# STM32G030_HeaderBoardSCH.net
KiCad netlist of a schematic drawn in Altium Designer
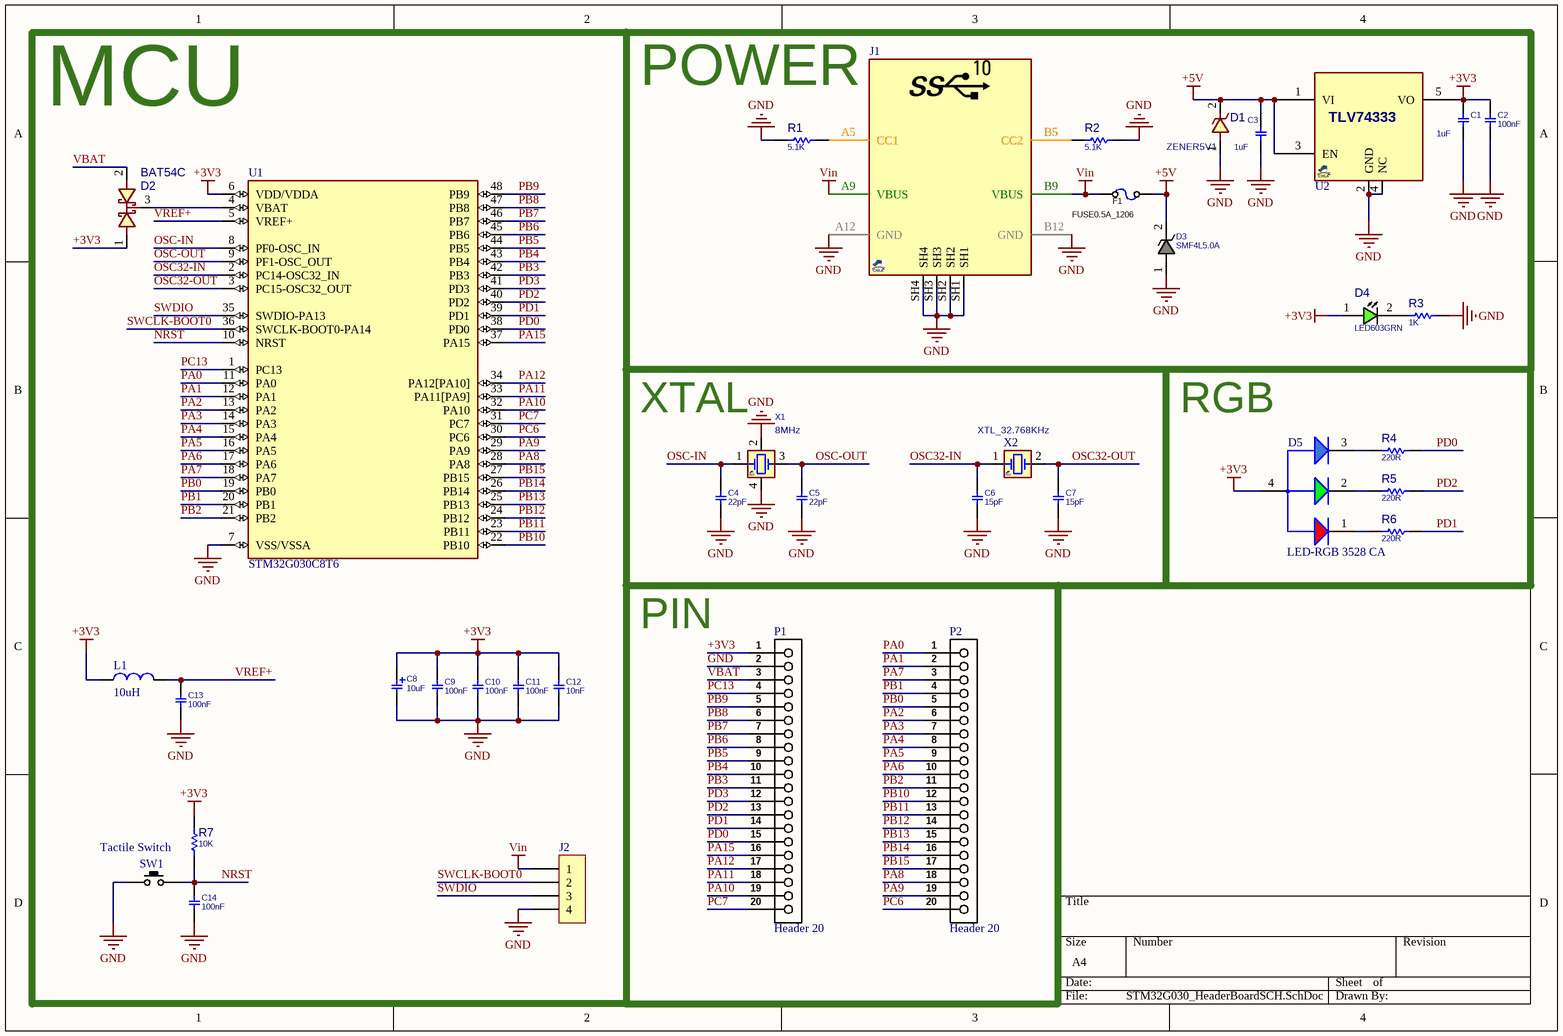
[diagram p0: STM32G030_HeaderBoardSCH.SchDoc]

(export (version "E")
  (design (tool "Eeschema 10.0.6"))
  (components
    (comp (ref "C1")
      (value "1uF")
      (footprint "C0603")
      (description "CAP, MLCC, -F, -V, MATERIAL, -%, 0201")
      (fields (field (name "MANF_P#") "MANF_PART#"))
      (libsource (lib "passive_smd") (part "CAP_SMD_MLCC_0603"))
    )
    (comp (ref "C2")
      (value "100nF")
      (footprint "C0603")
      (description "CAP, MLCC, -F, -V, MATERIAL, -%, 0201")
      (fields (field (name "MANF_P#") "MANF_PART#"))
      (libsource (lib "passive_smd") (part "CAP_SMD_MLCC_0603"))
    )
    (comp (ref "C3")
      (value "1uF")
      (footprint "C0603")
      (description "CAP, MLCC, -F, -V, MATERIAL, -%, 0201")
      (fields (field (name "MANF_P#") "MANF_PART#"))
      (libsource (lib "passive_smd") (part "CAP_SMD_MLCC_0603"))
    )
    (comp (ref "C4")
      (value "22pF")
      (footprint "C0603")
      (description "CAP, MLCC, -F, -V, MATERIAL, -%, 0201")
      (fields (field (name "MANF_P#") "MANF_PART#"))
      (libsource (lib "passive_smd") (part "CAP_SMD_MLCC_0603"))
    )
    (comp (ref "C5")
      (value "22pF")
      (footprint "C0603")
      (description "CAP, MLCC, -F, -V, MATERIAL, -%, 0201")
      (fields (field (name "MANF_P#") "MANF_PART#"))
      (libsource (lib "passive_smd") (part "CAP_SMD_MLCC_0603"))
    )
    (comp (ref "C6")
      (value "15pF")
      (footprint "C0603")
      (description "CAP, MLCC, -F, -V, MATERIAL, -%, 0201")
      (fields (field (name "MANF_P#") "MANF_PART#"))
      (libsource (lib "passive_smd") (part "CAP_SMD_MLCC_0603"))
    )
    (comp (ref "C7")
      (value "15pF")
      (footprint "C0603")
      (description "CAP, MLCC, -F, -V, MATERIAL, -%, 0201")
      (fields (field (name "MANF_P#") "MANF_PART#"))
      (libsource (lib "passive_smd") (part "CAP_SMD_MLCC_0603"))
    )
    (comp (ref "C8")
      (value "10uF")
      (footprint "C_TN_3216")
      (description "CAP, SMD, TAN,")
      (libsource (lib "passive_smd") (part "CAP_SMD_TAN"))
    )
    (comp (ref "C9")
      (value "100nF")
      (footprint "C0603")
      (description "CAP, MLCC, -F, -V, MATERIAL, -%, 0201")
      (fields (field (name "MANF_P#") "MANF_PART#"))
      (libsource (lib "passive_smd") (part "CAP_SMD_MLCC_0603"))
    )
    (comp (ref "C10")
      (value "100nF")
      (footprint "C0603")
      (description "CAP, MLCC, -F, -V, MATERIAL, -%, 0201")
      (fields (field (name "MANF_P#") "MANF_PART#"))
      (libsource (lib "passive_smd") (part "CAP_SMD_MLCC_0603"))
    )
    (comp (ref "C11")
      (value "100nF")
      (footprint "C0603")
      (description "CAP, MLCC, -F, -V, MATERIAL, -%, 0201")
      (fields (field (name "MANF_P#") "MANF_PART#"))
      (libsource (lib "passive_smd") (part "CAP_SMD_MLCC_0603"))
    )
    (comp (ref "C12")
      (value "10nF")
      (footprint "C0603")
      (description "CAP, MLCC, -F, -V, MATERIAL, -%, 0201")
      (fields (field (name "MANF_P#") "MANF_PART#"))
      (libsource (lib "passive_smd") (part "CAP_SMD_MLCC_0603"))
    )
    (comp (ref "C13")
      (value "100nF")
      (footprint "C0603")
      (description "CAP, MLCC, -F, -V, MATERIAL, -%, 0201")
      (fields (field (name "MANF_P#") "MANF_PART#"))
      (libsource (lib "passive_smd") (part "CAP_SMD_MLCC_0603"))
    )
    (comp (ref "C14")
      (value "100nF")
      (footprint "C0603")
      (description "CAP, MLCC, -F, -V, MATERIAL, -%, 0201")
      (fields (field (name "MANF_P#") "MANF_PART#"))
      (libsource (lib "passive_smd") (part "CAP_SMD_MLCC_0603"))
    )
    (comp (ref "D1")
      (value "ZENER5V1")
      (footprint "D_SOD123W")
      (description "DIODE, ZENER, 1W, 5.1V")
      (fields (field (name "MANF") "Diodes") (field (name "MANF_P#") "BZT52HC5V1WF-7"))
      (libsource (lib "AVR_RCS") (part "DIODE_SMD_ZENER_BZT52HC5V1"))
    )
    (comp (ref "D2")
      (value "BAT54C")
      (footprint "SOT23_3")
      (description "DIODE, SCHOTTKY, DUAL, 30V, 0.2A")
      (fields (field (name "MANF") "Diodes") (field (name "MANF_P#") "BAT54C-7-F"))
      (libsource (lib "diode") (part "DIODE_SMD_SCHOTTKY_BAT54C"))
    )
    (comp (ref "D3")
      (value "SMF4L5.0A")
      (footprint "D_SOD123W")
      (description "TVS, ESD PROTECT")
      (fields (field (name "MANF_P#") "TPSMF4L33A") (field (name "MANF") "Littelfuse"))
      (libsource (lib "protect_tvs_esd_fuse") (part "TVS_TPSMF4L33A"))
    )
    (comp (ref "D4")
      (value "LED603GRN")
      (footprint "LED0603GRN")
      (description "LED, SMD, 0603, GREEN")
      (fields (field (name "MANF") "Kingbright") (field (name "MANF_P#") "APT1608SGC"))
      (libsource (lib "led(diode)") (part "LED_SMD_0603_GRN"))
    )
    (comp (ref "D5")
      (value "LED-RGB 3528 CA")
      (footprint "LED-RGB 3528 CA")
      (description "LED SMD 3528 RGB-CA")
      (libsource (lib "Mehrdad") (part "LED-RGB 3528 CA"))
    )
    (comp (ref "F1")
      (value "FUSE0.5A_1206")
      (footprint "F1206")
      (description "Fuse, 3A, 32VDC, 1206, SMD, Slow Blow")
      (fields (field (name "MANF") "Bourns") (field (name "MANF_P#") "SF-1206SP300-2"))
      (libsource (lib "protect_tvs_esd_fuse") (part "FUSE_3A_1206_SLOW"))
    )
    (comp (ref "J1")
      (value "UJC-HP-3-SMT")
      (footprint "USBC_SMD_6_UJCHP3SMT")
      (description "CONN, USB, Type C (USB 3.1), Right-Angle, SMD")
      (fields (field (name "MANF") "CUI Devices"))
      (libsource (lib "conn_usbc") (part "CONN_USBC_SMD_6_UJC-HP-3-SMT"))
    )
    (comp (ref "J2")
      (value "4b")
      (footprint "HDR_THT_4M_2.54mm_RA")
      (description "Header, single row, 4 pin")
      (fields (field (name "VALIDATION") "NT"))
      (libsource (lib "aKaReZa") (part "Con_MPH_4x1_V_THT_2.54"))
    )
    (comp (ref "L1")
      (value "10uH")
      (footprint "0603_L")
      (description "Inductor")
      (fields (field (name "VALIDATION") "Valid"))
      (libsource (lib "aKaReZa") (part "Ind_SMD"))
    )
    (comp (ref "P1")
      (value "Header 20")
      (footprint "HDR 1X20 Male Top")
      (fields (field (name "PUBLISHER") "Majid Derhambakhsh"))
      (libsource (lib "mBedLab Altium Library (2024-04-20)") (part "Header 20"))
    )
    (comp (ref "P2")
      (value "Header 20")
      (footprint "HDR 1X20 Male Top")
      (fields (field (name "PUBLISHER") "Majid Derhambakhsh"))
      (libsource (lib "mBedLab Altium Library (2024-04-20)") (part "Header 20"))
    )
    (comp (ref "R1")
      (value "5.1K")
      (footprint "R0603")
      (description "RESISTOR, SMD")
      (libsource (lib "passive_smd") (part "RES_SMD_0603"))
    )
    (comp (ref "R2")
      (value "5.1K")
      (footprint "R0603")
      (description "RESISTOR, SMD")
      (libsource (lib "passive_smd") (part "RES_SMD_0603"))
    )
    (comp (ref "R3")
      (value "1K")
      (footprint "R0603")
      (description "RESISTOR, SMD")
      (libsource (lib "passive_smd") (part "RES_SMD_0603"))
    )
    (comp (ref "R4")
      (value "220R")
      (footprint "R0603")
      (description "RESISTOR, SMD")
      (libsource (lib "passive_smd") (part "RES_SMD_0603"))
    )
    (comp (ref "R5")
      (value "220R")
      (footprint "R0603")
      (description "RESISTOR, SMD")
      (libsource (lib "passive_smd") (part "RES_SMD_0603"))
    )
    (comp (ref "R6")
      (value "220R")
      (footprint "R0603")
      (description "RESISTOR, SMD")
      (libsource (lib "passive_smd") (part "RES_SMD_0603"))
    )
    (comp (ref "R7")
      (value "10K")
      (footprint "R0603")
      (description "RESISTOR, SMD")
      (libsource (lib "passive_smd") (part "RES_SMD_0603"))
    )
    (comp (ref "SW1")
      (value "Tactile Switch")
      (footprint "Tactil Switch 3*4*2")
      (description "3x6x5 mm - 2 Pin")
      (libsource (lib "Mehrdad") (part "Tactile Switch"))
    )
    (comp (ref "U1")
      (value "STM32G030C8T6")
      (footprint "STM32G030C8T6")
      (libsource (lib "Mehrdad") (part "STM32G030C8T6"))
    )
    (comp (ref "U2")
      (value "TLV74333")
      (footprint "SOT23_5")
      (description "REG, Linear, LDO0.12V, Fixed, 300mA, VIN1.4~5.5V, VOUT1~5.5V, SOT-23-5")
      (fields (field (name "MANF") "Texas Instruments") (field (name "MANF_P#") "TLV74333PDQN"))
      (libsource (lib "pwr_reg_linear_LDO_highPSRR") (part "VREG_TLV74333_SOT23"))
    )
    (comp (ref "X1")
      (value "8MHz")
      (footprint "XTL_4_3225")
      (description "Crystal 8MHz")
      (fields (field (name "MANF") "ECS") (field (name "MANF_P#") "ECS-80-18-33-JGN-TR"))
      (libsource (lib "crystal") (part "XTL_4_8MHz_3225"))
    )
    (comp (ref "X2")
      (value "XTL_32.768KHz")
      (footprint "XTL_2_3215")
      (description "Crystal, 32.768KHz, 3pF, 20PPM")
      (fields (field (name "MANF") "ABRACON") (field (name "MANF_P#") "ABS07W-32.768kHz-D-2-T"))
      (libsource (lib "crystal") (part "XTL_2_32.768_3215A"))
    )
  )
  (nets
    (net (code "1") (name "+3V3") (class "Default")
      (node (ref "C1") (pin "2") (pinfunction "2_2") (pintype "passive"))
      (node (ref "C10") (pin "2") (pinfunction "2_2") (pintype "passive"))
      (node (ref "C11") (pin "2") (pinfunction "2_2") (pintype "passive"))
      (node (ref "C12") (pin "2") (pinfunction "2_2") (pintype "passive"))
      (node (ref "C2") (pin "2") (pinfunction "2_2") (pintype "passive"))
      (node (ref "C8") (pin "1") (pinfunction "1_1") (pintype "passive"))
      (node (ref "C9") (pin "2") (pinfunction "2_2") (pintype "passive"))
      (node (ref "D2") (pin "1") (pinfunction "1_1") (pintype "passive"))
      (node (ref "D4") (pin "1") (pinfunction "ANODE_1") (pintype "passive"))
      (node (ref "D5") (pin "4") (pinfunction "COMM_ANODE_4") (pintype "passive"))
      (node (ref "L1") (pin "1") (pinfunction "1_1") (pintype "passive"))
      (node (ref "P1") (pin "1") (pinfunction "1_1") (pintype "passive"))
      (node (ref "R7") (pin "2") (pinfunction "2_2") (pintype "passive"))
      (node (ref "U1") (pin "6") (pinfunction "VDD/VDDA_6") (pintype "bidirectional"))
      (node (ref "U2") (pin "5") (pinfunction "VO_5") (pintype "passive"))
    )
    (net (code "2") (name "+5V") (class "Default")
      (node (ref "C3") (pin "2") (pinfunction "2_2") (pintype "passive"))
      (node (ref "D1") (pin "2") (pinfunction "2_2") (pintype "passive"))
      (node (ref "D3") (pin "2") (pinfunction "2_2") (pintype "passive"))
      (node (ref "F1") (pin "2") (pinfunction "2_2") (pintype "passive"))
      (node (ref "U2") (pin "1") (pinfunction "VI_1") (pintype "passive"))
      (node (ref "U2") (pin "3") (pinfunction "EN_3") (pintype "passive"))
    )
    (net (code "3") (name "/NRST") (class "Default")
      (node (ref "C14") (pin "2") (pinfunction "2_2") (pintype "passive"))
      (node (ref "R7") (pin "1") (pinfunction "1_1") (pintype "passive"))
      (node (ref "SW1") (pin "2") (pinfunction "P3_2") (pintype "passive"))
      (node (ref "U1") (pin "10") (pinfunction "NRST_10") (pintype "bidirectional"))
    )
    (net (code "4") (name "/OSC-IN") (class "Default")
      (node (ref "C4") (pin "2") (pinfunction "2_2") (pintype "passive"))
      (node (ref "U1") (pin "8") (pinfunction "PF0-OSC_IN_8") (pintype "bidirectional"))
      (node (ref "X1") (pin "1") (pinfunction "1_1") (pintype "passive"))
    )
    (net (code "5") (name "/OSC-OUT") (class "Default")
      (node (ref "C5") (pin "2") (pinfunction "2_2") (pintype "passive"))
      (node (ref "U1") (pin "9") (pinfunction "PF1-OSC_OUT_9") (pintype "bidirectional"))
      (node (ref "X1") (pin "3") (pinfunction "2_3") (pintype "passive"))
    )
    (net (code "6") (name "/OSC32-IN") (class "Default")
      (node (ref "C6") (pin "2") (pinfunction "2_2") (pintype "passive"))
      (node (ref "U1") (pin "2") (pinfunction "PC14-OSC32_IN_2") (pintype "bidirectional"))
      (node (ref "X2") (pin "1") (pinfunction "OSC1_1") (pintype "passive"))
    )
    (net (code "7") (name "/OSC32-OUT") (class "Default")
      (node (ref "C7") (pin "2") (pinfunction "2_2") (pintype "passive"))
      (node (ref "U1") (pin "3") (pinfunction "PC15-OSC32_OUT_3") (pintype "bidirectional"))
      (node (ref "X2") (pin "2") (pinfunction "OSC2_2") (pintype "passive"))
    )
    (net (code "8") (name "/PA0") (class "Default")
      (node (ref "P2") (pin "1") (pinfunction "1_1") (pintype "passive"))
      (node (ref "U1") (pin "11") (pinfunction "PA0_11") (pintype "bidirectional"))
    )
    (net (code "9") (name "/PA1") (class "Default")
      (node (ref "P2") (pin "2") (pinfunction "2_2") (pintype "passive"))
      (node (ref "U1") (pin "12") (pinfunction "PA1_12") (pintype "bidirectional"))
    )
    (net (code "10") (name "/PA2") (class "Default")
      (node (ref "P2") (pin "6") (pinfunction "6_6") (pintype "passive"))
      (node (ref "U1") (pin "13") (pinfunction "PA2_13") (pintype "bidirectional"))
    )
    (net (code "11") (name "/PA3") (class "Default")
      (node (ref "P2") (pin "7") (pinfunction "7_7") (pintype "passive"))
      (node (ref "U1") (pin "14") (pinfunction "PA3_14") (pintype "bidirectional"))
    )
    (net (code "12") (name "/PA4") (class "Default")
      (node (ref "P2") (pin "8") (pinfunction "8_8") (pintype "passive"))
      (node (ref "U1") (pin "15") (pinfunction "PA4_15") (pintype "bidirectional"))
    )
    (net (code "13") (name "/PA5") (class "Default")
      (node (ref "P2") (pin "9") (pinfunction "9_9") (pintype "passive"))
      (node (ref "U1") (pin "16") (pinfunction "PA5_16") (pintype "bidirectional"))
    )
    (net (code "14") (name "/PA6") (class "Default")
      (node (ref "P2") (pin "10") (pinfunction "10_10") (pintype "passive"))
      (node (ref "U1") (pin "17") (pinfunction "PA6_17") (pintype "bidirectional"))
    )
    (net (code "15") (name "/PA7") (class "Default")
      (node (ref "P2") (pin "3") (pinfunction "3_3") (pintype "passive"))
      (node (ref "U1") (pin "18") (pinfunction "PA7_18") (pintype "bidirectional"))
    )
    (net (code "16") (name "/PA8") (class "Default")
      (node (ref "P2") (pin "18") (pinfunction "18_18") (pintype "passive"))
      (node (ref "U1") (pin "28") (pinfunction "PA8_28") (pintype "bidirectional"))
    )
    (net (code "17") (name "/PA9") (class "Default")
      (node (ref "P2") (pin "19") (pinfunction "19_19") (pintype "passive"))
      (node (ref "U1") (pin "29") (pinfunction "PA9_29") (pintype "bidirectional"))
    )
    (net (code "18") (name "/PA10") (class "Default")
      (node (ref "P1") (pin "19") (pinfunction "19_19") (pintype "passive"))
      (node (ref "U1") (pin "32") (pinfunction "PA10_32") (pintype "bidirectional"))
    )
    (net (code "19") (name "/PA11") (class "Default")
      (node (ref "P1") (pin "18") (pinfunction "18_18") (pintype "passive"))
      (node (ref "U1") (pin "33") (pinfunction "PA11[PA9]_33") (pintype "bidirectional"))
    )
    (net (code "20") (name "/PA12") (class "Default")
      (node (ref "P1") (pin "17") (pinfunction "17_17") (pintype "passive"))
      (node (ref "U1") (pin "34") (pinfunction "PA12[PA10]_34") (pintype "bidirectional"))
    )
    (net (code "21") (name "/PA15") (class "Default")
      (node (ref "P1") (pin "16") (pinfunction "16_16") (pintype "passive"))
      (node (ref "U1") (pin "37") (pinfunction "PA15_37") (pintype "bidirectional"))
    )
    (net (code "22") (name "/PB0") (class "Default")
      (node (ref "P2") (pin "5") (pinfunction "5_5") (pintype "passive"))
      (node (ref "U1") (pin "19") (pinfunction "PB0_19") (pintype "bidirectional"))
    )
    (net (code "23") (name "/PB1") (class "Default")
      (node (ref "P2") (pin "4") (pinfunction "4_4") (pintype "passive"))
      (node (ref "U1") (pin "20") (pinfunction "PB1_20") (pintype "bidirectional"))
    )
    (net (code "24") (name "/PB2") (class "Default")
      (node (ref "P2") (pin "11") (pinfunction "11_11") (pintype "passive"))
      (node (ref "U1") (pin "21") (pinfunction "PB2_21") (pintype "bidirectional"))
    )
    (net (code "25") (name "/PB3") (class "Default")
      (node (ref "P1") (pin "11") (pinfunction "11_11") (pintype "passive"))
      (node (ref "U1") (pin "42") (pinfunction "PB3_42") (pintype "bidirectional"))
    )
    (net (code "26") (name "/PB4") (class "Default")
      (node (ref "P1") (pin "10") (pinfunction "10_10") (pintype "passive"))
      (node (ref "U1") (pin "43") (pinfunction "PB4_43") (pintype "bidirectional"))
    )
    (net (code "27") (name "/PB5") (class "Default")
      (node (ref "P1") (pin "9") (pinfunction "9_9") (pintype "passive"))
      (node (ref "U1") (pin "44") (pinfunction "PB5_44") (pintype "bidirectional"))
    )
    (net (code "28") (name "/PB6") (class "Default")
      (node (ref "P1") (pin "8") (pinfunction "8_8") (pintype "passive"))
      (node (ref "U1") (pin "45") (pinfunction "PB6_45") (pintype "bidirectional"))
    )
    (net (code "29") (name "/PB7") (class "Default")
      (node (ref "P1") (pin "7") (pinfunction "7_7") (pintype "passive"))
      (node (ref "U1") (pin "46") (pinfunction "PB7_46") (pintype "bidirectional"))
    )
    (net (code "30") (name "/PB8") (class "Default")
      (node (ref "P1") (pin "6") (pinfunction "6_6") (pintype "passive"))
      (node (ref "U1") (pin "47") (pinfunction "PB8_47") (pintype "bidirectional"))
    )
    (net (code "31") (name "/PB9") (class "Default")
      (node (ref "P1") (pin "5") (pinfunction "5_5") (pintype "passive"))
      (node (ref "U1") (pin "48") (pinfunction "PB9_48") (pintype "bidirectional"))
    )
    (net (code "32") (name "/PB10") (class "Default")
      (node (ref "P2") (pin "12") (pinfunction "12_12") (pintype "passive"))
      (node (ref "U1") (pin "22") (pinfunction "PB10_22") (pintype "bidirectional"))
    )
    (net (code "33") (name "/PB11") (class "Default")
      (node (ref "P2") (pin "13") (pinfunction "13_13") (pintype "passive"))
      (node (ref "U1") (pin "23") (pinfunction "PB11_23") (pintype "bidirectional"))
    )
    (net (code "34") (name "/PB12") (class "Default")
      (node (ref "P2") (pin "14") (pinfunction "14_14") (pintype "passive"))
      (node (ref "U1") (pin "24") (pinfunction "PB12_24") (pintype "bidirectional"))
    )
    (net (code "35") (name "/PB13") (class "Default")
      (node (ref "P2") (pin "15") (pinfunction "15_15") (pintype "passive"))
      (node (ref "U1") (pin "25") (pinfunction "PB13_25") (pintype "bidirectional"))
    )
    (net (code "36") (name "/PB14") (class "Default")
      (node (ref "P2") (pin "16") (pinfunction "16_16") (pintype "passive"))
      (node (ref "U1") (pin "26") (pinfunction "PB14_26") (pintype "bidirectional"))
    )
    (net (code "37") (name "/PB15") (class "Default")
      (node (ref "P2") (pin "17") (pinfunction "17_17") (pintype "passive"))
      (node (ref "U1") (pin "27") (pinfunction "PB15_27") (pintype "bidirectional"))
    )
    (net (code "38") (name "/PC6") (class "Default")
      (node (ref "P2") (pin "20") (pinfunction "20_20") (pintype "passive"))
      (node (ref "U1") (pin "30") (pinfunction "PC6_30") (pintype "bidirectional"))
    )
    (net (code "39") (name "/PC7") (class "Default")
      (node (ref "P1") (pin "20") (pinfunction "20_20") (pintype "passive"))
      (node (ref "U1") (pin "31") (pinfunction "PC7_31") (pintype "bidirectional"))
    )
    (net (code "40") (name "/PC13") (class "Default")
      (node (ref "P1") (pin "4") (pinfunction "4_4") (pintype "passive"))
      (node (ref "U1") (pin "1") (pinfunction "PC13_1") (pintype "bidirectional"))
    )
    (net (code "41") (name "/PD0") (class "Default")
      (node (ref "P1") (pin "15") (pinfunction "15_15") (pintype "passive"))
      (node (ref "R4") (pin "1") (pinfunction "1_1") (pintype "passive"))
      (node (ref "U1") (pin "38") (pinfunction "PD0_38") (pintype "bidirectional"))
    )
    (net (code "42") (name "/PD1") (class "Default")
      (node (ref "P1") (pin "14") (pinfunction "14_14") (pintype "passive"))
      (node (ref "R6") (pin "1") (pinfunction "1_1") (pintype "passive"))
      (node (ref "U1") (pin "39") (pinfunction "PD1_39") (pintype "bidirectional"))
    )
    (net (code "43") (name "/PD2") (class "Default")
      (node (ref "P1") (pin "13") (pinfunction "13_13") (pintype "passive"))
      (node (ref "R5") (pin "1") (pinfunction "1_1") (pintype "passive"))
      (node (ref "U1") (pin "40") (pinfunction "PD2_40") (pintype "bidirectional"))
    )
    (net (code "44") (name "/PD3") (class "Default")
      (node (ref "P1") (pin "12") (pinfunction "12_12") (pintype "passive"))
      (node (ref "U1") (pin "41") (pinfunction "PD3_41") (pintype "bidirectional"))
    )
    (net (code "45") (name "/SWCLK-BOOT0") (class "Default")
      (node (ref "J2") (pin "2") (pinfunction "2_2") (pintype "passive"))
      (node (ref "U1") (pin "36") (pinfunction "SWCLK-BOOT0-PA14_36") (pintype "bidirectional"))
    )
    (net (code "46") (name "/SWDIO") (class "Default")
      (node (ref "J2") (pin "3") (pinfunction "3_3") (pintype "passive"))
      (node (ref "U1") (pin "35") (pinfunction "SWDIO-PA13_35") (pintype "bidirectional"))
    )
    (net (code "47") (name "/VBAT") (class "Default")
      (node (ref "D2") (pin "2") (pinfunction "2_2") (pintype "passive"))
      (node (ref "P1") (pin "3") (pinfunction "3_3") (pintype "passive"))
    )
    (net (code "48") (name "/VREF+") (class "Default")
      (node (ref "C13") (pin "2") (pinfunction "2_2") (pintype "passive"))
      (node (ref "L1") (pin "2") (pinfunction "2_2") (pintype "passive"))
      (node (ref "U1") (pin "5") (pinfunction "VREF+_5") (pintype "bidirectional"))
    )
    (net (code "49") (name "GND") (class "Default")
      (node (ref "C1") (pin "1") (pinfunction "1_1") (pintype "passive"))
      (node (ref "C10") (pin "1") (pinfunction "1_1") (pintype "passive"))
      (node (ref "C11") (pin "1") (pinfunction "1_1") (pintype "passive"))
      (node (ref "C12") (pin "1") (pinfunction "1_1") (pintype "passive"))
      (node (ref "C13") (pin "1") (pinfunction "1_1") (pintype "passive"))
      (node (ref "C14") (pin "1") (pinfunction "1_1") (pintype "passive"))
      (node (ref "C2") (pin "1") (pinfunction "1_1") (pintype "passive"))
      (node (ref "C3") (pin "1") (pinfunction "1_1") (pintype "passive"))
      (node (ref "C4") (pin "1") (pinfunction "1_1") (pintype "passive"))
      (node (ref "C5") (pin "1") (pinfunction "1_1") (pintype "passive"))
      (node (ref "C6") (pin "1") (pinfunction "1_1") (pintype "passive"))
      (node (ref "C7") (pin "1") (pinfunction "1_1") (pintype "passive"))
      (node (ref "C8") (pin "2") (pinfunction "2_2") (pintype "passive"))
      (node (ref "C9") (pin "1") (pinfunction "1_1") (pintype "passive"))
      (node (ref "D1") (pin "1") (pinfunction "1_1") (pintype "passive"))
      (node (ref "D3") (pin "1") (pinfunction "1_1") (pintype "passive"))
      (node (ref "J1") (pin "A12") (pinfunction "GND_A12") (pintype "passive"))
      (node (ref "J1") (pin "B12") (pinfunction "GND_B12") (pintype "passive"))
      (node (ref "J1") (pin "SH1") (pinfunction "SH1_SH1") (pintype "passive"))
      (node (ref "J1") (pin "SH2") (pinfunction "SH2_SH2") (pintype "passive"))
      (node (ref "J1") (pin "SH3") (pinfunction "SH3_SH3") (pintype "passive"))
      (node (ref "J1") (pin "SH4") (pinfunction "SH4_SH4") (pintype "passive"))
      (node (ref "J2") (pin "4") (pinfunction "4_4") (pintype "passive"))
      (node (ref "P1") (pin "2") (pinfunction "2_2") (pintype "passive"))
      (node (ref "R1") (pin "2") (pinfunction "2_2") (pintype "passive"))
      (node (ref "R2") (pin "1") (pinfunction "1_1") (pintype "passive"))
      (node (ref "R3") (pin "1") (pinfunction "1_1") (pintype "passive"))
      (node (ref "SW1") (pin "1") (pinfunction "P1_1") (pintype "passive"))
      (node (ref "U1") (pin "7") (pinfunction "VSS/VSSA_7") (pintype "bidirectional"))
      (node (ref "U2") (pin "2") (pinfunction "GND_2") (pintype "passive"))
      (node (ref "U2") (pin "4") (pinfunction "NC_4") (pintype "passive"))
      (node (ref "X1") (pin "2") (pinfunction "2_2") (pintype "passive"))
      (node (ref "X1") (pin "4") (pinfunction "4_4") (pintype "passive"))
    )
    (net (code "50") (name "Net-(D4-CATHODE)") (class "Default")
      (node (ref "D4") (pin "2") (pinfunction "CATHODE_2") (pintype "passive"))
      (node (ref "R3") (pin "2") (pinfunction "2_2") (pintype "passive"))
    )
    (net (code "51") (name "Net-(D5-CATHODE_BLUE)") (class "Default")
      (node (ref "D5") (pin "3") (pinfunction "CATHODE_BLUE_3") (pintype "passive"))
      (node (ref "R4") (pin "2") (pinfunction "2_2") (pintype "passive"))
    )
    (net (code "52") (name "Net-(D5-CATHODE_GREEN)") (class "Default")
      (node (ref "D5") (pin "2") (pinfunction "CATHODE_GREEN_2") (pintype "passive"))
      (node (ref "R5") (pin "2") (pinfunction "2_2") (pintype "passive"))
    )
    (net (code "53") (name "Net-(D5-CATHODE_RED)") (class "Default")
      (node (ref "D5") (pin "1") (pinfunction "CATHODE_RED_1") (pintype "passive"))
      (node (ref "R6") (pin "2") (pinfunction "2_2") (pintype "passive"))
    )
    (net (code "54") (name "Net-(J1-CC1)") (class "Default")
      (node (ref "J1") (pin "A5") (pinfunction "CC1_A5") (pintype "passive"))
      (node (ref "R1") (pin "1") (pinfunction "1_1") (pintype "passive"))
    )
    (net (code "55") (name "Net-(J1-CC2)") (class "Default")
      (node (ref "J1") (pin "B5") (pinfunction "CC2_B5") (pintype "passive"))
      (node (ref "R2") (pin "2") (pinfunction "2_2") (pintype "passive"))
    )
    (net (code "56") (name "Net-(U1-VBAT)") (class "Default")
      (node (ref "D2") (pin "3") (pinfunction "3_3") (pintype "passive"))
      (node (ref "U1") (pin "4") (pinfunction "VBAT_4") (pintype "bidirectional"))
    )
    (net (code "57") (name "Vin") (class "Default")
      (node (ref "F1") (pin "1") (pinfunction "1_1") (pintype "passive"))
      (node (ref "J1") (pin "A9") (pinfunction "VBUS_A9") (pintype "passive"))
      (node (ref "J1") (pin "B9") (pinfunction "VBUS_B9") (pintype "passive"))
      (node (ref "J2") (pin "1") (pinfunction "1_1") (pintype "passive"))
    )
  )
)
